# Sheet1.net
KiCad netlist of a schematic drawn in Altium Designer
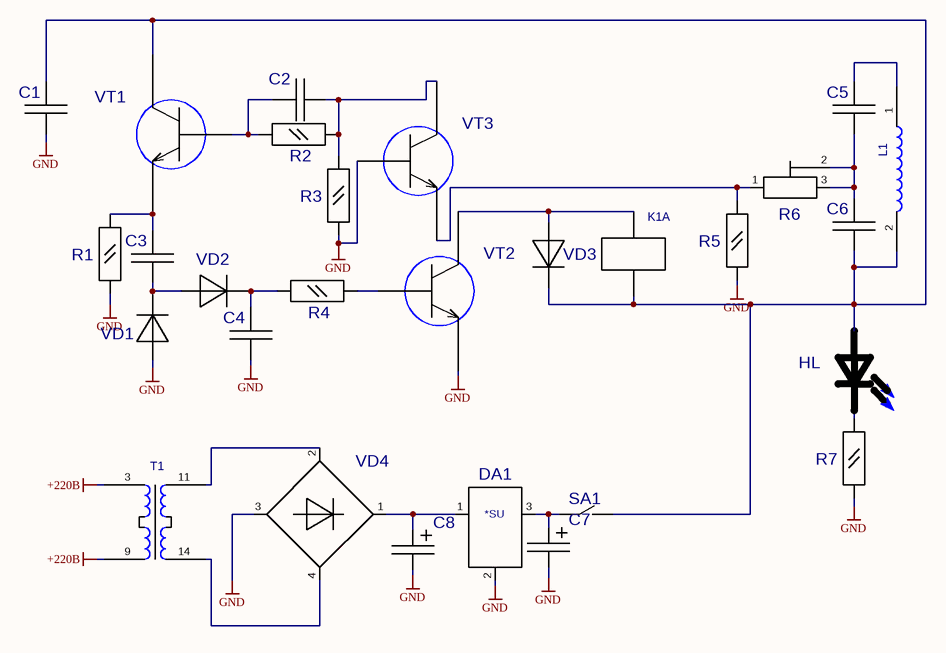
[diagram p0: Sheet1.SCHDOC]

(export (version "E")
  (design (tool "Eeschema 10.0.6"))
  (components
    (comp (ref "C1")
      (value "B32921-C3103-0,01UF")
      (footprint "B32921(13X4)")
      (libsource (lib "*") (part "B32921-C3103-0,01UF"))
    )
    (comp (ref "C2")
      (value "B32921-C3103-0,01UF")
      (footprint "B32921(13X4)")
      (libsource (lib "*") (part "B32921-C3103-0,01UF"))
    )
    (comp (ref "C3")
      (value "B32921-C3103-0,01UF")
      (footprint "B32921(13X4)")
      (libsource (lib "*") (part "B32921-C3103-0,01UF"))
    )
    (comp (ref "C4")
      (value "B32921-C3103-0,01UF")
      (footprint "B32921(13X4)")
      (libsource (lib "*") (part "B32921-C3103-0,01UF"))
    )
    (comp (ref "C5")
      (value "B32921-C3103-0,01UF")
      (footprint "B32921(13X4)")
      (libsource (lib "*") (part "B32921-C3103-0,01UF"))
    )
    (comp (ref "C6")
      (value "B32921-C3103-0,01UF")
      (footprint "B32921(13X4)")
      (libsource (lib "*") (part "B32921-C3103-0,01UF"))
    )
    (comp (ref "C7") (value "COND-PL-EL") (footprint "CC-PL-EL1") (libsource (lib "*") (part "COND-PL-EL")))
    (comp (ref "C8") (value "COND-PL-EL") (footprint "CC-PL-EL1") (libsource (lib "*") (part "COND-PL-EL")))
    (comp (ref "DA1") (value "KR142EN") (footprint "KR142EN") (libsource (lib "*") (part "KR142EN")))
    (comp (ref "HL") (value "КИПД21-К") (footprint "LED-5MM") (libsource (lib "*") (part "КИПД21-К")))
    (comp (ref "K1") (value "РЭС6") (footprint "РЭС6") (libsource (lib "*") (part "РЭС6")))
    (comp (ref "L1") (value "L") (footprint "L") (libsource (lib "*") (part "L")))
    (comp (ref "R1")
      (value "C2-33H-0.125W_OLD_UGO")
      (footprint "C2-33H-0.125W")
      (fields (field (name "AUTOR") "pcbdesigner.ru"))
      (libsource (lib "*") (part "C2-33H-0.125W_OLD_UGO"))
    )
    (comp (ref "R2")
      (value "C2-33H-0.125W_OLD_UGO")
      (footprint "C2-33H-0.125W")
      (fields (field (name "AUTOR") "pcbdesigner.ru"))
      (libsource (lib "*") (part "C2-33H-0.125W_OLD_UGO"))
    )
    (comp (ref "R3")
      (value "C2-33H-0.125W_OLD_UGO")
      (footprint "C2-33H-0.125W")
      (fields (field (name "AUTOR") "pcbdesigner.ru"))
      (libsource (lib "*") (part "C2-33H-0.125W_OLD_UGO"))
    )
    (comp (ref "R4")
      (value "C2-33H-0.125W_OLD_UGO")
      (footprint "C2-33H-0.125W")
      (fields (field (name "AUTOR") "pcbdesigner.ru"))
      (libsource (lib "*") (part "C2-33H-0.125W_OLD_UGO"))
    )
    (comp (ref "R5")
      (value "C2-33H-0.125W_OLD_UGO")
      (footprint "C2-33H-0.125W")
      (fields (field (name "AUTOR") "pcbdesigner.ru"))
      (libsource (lib "*") (part "C2-33H-0.125W_OLD_UGO"))
    )
    (comp (ref "R6") (value "SP3-19A1") (footprint "SP3-19A1") (libsource (lib "*") (part "SP3-19A1")))
    (comp (ref "R7")
      (value "C2-33H-0.125W_OLD_UGO")
      (footprint "C2-33H-0.125W")
      (fields (field (name "AUTOR") "pcbdesigner.ru"))
      (libsource (lib "*") (part "C2-33H-0.125W_OLD_UGO"))
    )
    (comp (ref "SA1")
      (value "8AS9M2RE")
      (footprint "8AS9M2RE")
      (fields (field (name "AUTHOR") "pcbdesigner.ru"))
      (libsource (lib "*") (part "8AS9M2RE"))
    )
    (comp (ref "T1") (value "ТПП277") (footprint "ТПП") (libsource (lib "*") (part "ТПП277")))
    (comp (ref "VD1") (value "DO27") (footprint "DO27") (libsource (lib "*") (part "DO27")))
    (comp (ref "VD2") (value "DO27") (footprint "DO27") (libsource (lib "*") (part "DO27")))
    (comp (ref "VD3") (value "DO27") (footprint "DO27") (libsource (lib "*") (part "DO27")))
    (comp (ref "VD4") (value "KBU6A") (footprint "KBU6A") (libsource (lib "*") (part "KBU6A")))
    (comp (ref "VT1") (value "2N4401") (footprint "TO-92-1") (libsource (lib "*") (part "2N4401")))
    (comp (ref "VT2") (value "2N4401") (footprint "TO-92-1") (libsource (lib "*") (part "2N4401")))
    (comp (ref "VT3") (value "2N4401") (footprint "TO-92-1") (libsource (lib "*") (part "2N4401")))
  )
  (nets
    (net (code "1") (name "+220B") (class "Default")
      (node (ref "T1") (pin "3") (pintype "passive"))
      (node (ref "T1") (pin "9") (pintype "passive"))
    )
    (net (code "2") (name "GND") (class "Default")
      (node (ref "C1") (pin "2") (pinfunction "2_2") (pintype "passive"))
      (node (ref "C4") (pin "2") (pinfunction "2_2") (pintype "passive"))
      (node (ref "C7") (pin "2") (pinfunction "i/o1_2") (pintype "passive"))
      (node (ref "C8") (pin "2") (pinfunction "i/o1_2") (pintype "passive"))
      (node (ref "DA1") (pin "2") (pinfunction "GND0_2") (pintype "passive"))
      (node (ref "R1") (pin "2") (pinfunction "2_2") (pintype "passive"))
      (node (ref "R3") (pin "2") (pinfunction "2_2") (pintype "passive"))
      (node (ref "R5") (pin "2") (pinfunction "2_2") (pintype "passive"))
      (node (ref "R7") (pin "2") (pinfunction "2_2") (pintype "passive"))
      (node (ref "VD1") (pin "2") (pinfunction "I/O2_2") (pintype "passive"))
      (node (ref "VD4") (pin "3") (pinfunction "3_3") (pintype "passive"))
      (node (ref "VT2") (pin "1") (pinfunction "E_1") (pintype "passive"))
      (node (ref "VT3") (pin "2") (pinfunction "B_2") (pintype "passive"))
    )
    (net (code "3") (name "Net-(C5-Pad1)") (class "Default")
      (node (ref "C5") (pin "1") (pinfunction "1_1") (pintype "passive"))
      (node (ref "L1") (pin "1") (pintype "passive"))
    )
    (net (code "4") (name "Net-(C7-i{slash}o)") (class "Default")
      (node (ref "C7") (pin "1") (pinfunction "i/o_1") (pintype "passive"))
      (node (ref "DA1") (pin "3") (pinfunction "OUT0_3") (pintype "passive"))
      (node (ref "SA1") (pin "2") (pinfunction "2_2") (pintype "passive"))
    )
    (net (code "5") (name "Net-(C8-i{slash}o)") (class "Default")
      (node (ref "C8") (pin "1") (pinfunction "i/o_1") (pintype "passive"))
      (node (ref "DA1") (pin "1") (pinfunction "IN0_1") (pintype "passive"))
      (node (ref "VD4") (pin "1") (pinfunction "1_1") (pintype "passive"))
    )
    (net (code "6") (name "Net-(HL-A)") (class "Default")
      (node (ref "C1") (pin "1") (pinfunction "1_1") (pintype "passive"))
      (node (ref "C6") (pin "2") (pinfunction "2_2") (pintype "passive"))
      (node (ref "HL") (pin "1") (pinfunction "A_1") (pintype "passive"))
      (node (ref "K1") (pin "8") (pinfunction "3_8") (pintype "passive"))
      (node (ref "L1") (pin "2") (pintype "passive"))
      (node (ref "SA1") (pin "1") (pinfunction "1_1") (pintype "passive"))
      (node (ref "VD3") (pin "1") (pinfunction "I/O1_1") (pintype "passive"))
      (node (ref "VT1") (pin "3") (pinfunction "K_3") (pintype "passive"))
    )
    (net (code "7") (name "Net-(HL-K)") (class "Default")
      (node (ref "HL") (pin "2") (pinfunction "K_2") (pintype "passive"))
      (node (ref "R7") (pin "1") (pinfunction "1_1") (pintype "passive"))
    )
    (net (code "8") (name "Net-(K1-1)") (class "Default")
      (node (ref "K1") (pin "7") (pinfunction "1_7") (pintype "passive"))
      (node (ref "VD3") (pin "2") (pinfunction "I/O2_2") (pintype "passive"))
      (node (ref "VT2") (pin "3") (pinfunction "K_3") (pintype "passive"))
    )
    (net (code "9") (name "Net-(R6-I{slash}O1)") (class "Default")
      (node (ref "R5") (pin "1") (pinfunction "1_1") (pintype "passive"))
      (node (ref "R6") (pin "1") (pinfunction "I/O1_1") (pintype "passive"))
      (node (ref "VT3") (pin "1") (pinfunction "E_1") (pintype "passive"))
    )
    (net (code "10") (name "Net-(R6-I{slash}O2)") (class "Default")
      (node (ref "C5") (pin "2") (pinfunction "2_2") (pintype "passive"))
      (node (ref "C6") (pin "1") (pinfunction "1_1") (pintype "passive"))
      (node (ref "R6") (pin "2") (pinfunction "I/O2_2") (pintype "passive"))
      (node (ref "R6") (pin "3") (pinfunction "I/O3_3") (pintype "passive"))
    )
    (net (code "11") (name "Net-(T1-Pad11)") (class "Default")
      (node (ref "T1") (pin "11") (pintype "passive"))
      (node (ref "VD4") (pin "2") (pinfunction "2_2") (pintype "passive"))
    )
    (net (code "12") (name "Net-(T1-Pad14)") (class "Default")
      (node (ref "T1") (pin "14") (pintype "passive"))
      (node (ref "VD4") (pin "4") (pinfunction "4_4") (pintype "passive"))
    )
    (net (code "13") (name "Net-(VD1-I{slash}O1)") (class "Default")
      (node (ref "C3") (pin "2") (pinfunction "2_2") (pintype "passive"))
      (node (ref "VD1") (pin "1") (pinfunction "I/O1_1") (pintype "passive"))
      (node (ref "VD2") (pin "2") (pinfunction "I/O2_2") (pintype "passive"))
    )
    (net (code "14") (name "Net-(VD2-I{slash}O1)") (class "Default")
      (node (ref "C4") (pin "1") (pinfunction "1_1") (pintype "passive"))
      (node (ref "R4") (pin "1") (pinfunction "1_1") (pintype "passive"))
      (node (ref "VD2") (pin "1") (pinfunction "I/O1_1") (pintype "passive"))
    )
    (net (code "15") (name "Net-(VT1-B)") (class "Default")
      (node (ref "C2") (pin "1") (pinfunction "1_1") (pintype "passive"))
      (node (ref "R2") (pin "1") (pinfunction "1_1") (pintype "passive"))
      (node (ref "VT1") (pin "2") (pinfunction "B_2") (pintype "passive"))
    )
    (net (code "16") (name "Net-(VT1-E)") (class "Default")
      (node (ref "C3") (pin "1") (pinfunction "1_1") (pintype "passive"))
      (node (ref "R1") (pin "1") (pinfunction "1_1") (pintype "passive"))
      (node (ref "VT1") (pin "1") (pinfunction "E_1") (pintype "passive"))
    )
    (net (code "17") (name "Net-(VT2-B)") (class "Default")
      (node (ref "R4") (pin "2") (pinfunction "2_2") (pintype "passive"))
      (node (ref "VT2") (pin "2") (pinfunction "B_2") (pintype "passive"))
    )
    (net (code "18") (name "Net-(VT3-K)") (class "Default")
      (node (ref "C2") (pin "2") (pinfunction "2_2") (pintype "passive"))
      (node (ref "R2") (pin "2") (pinfunction "2_2") (pintype "passive"))
      (node (ref "R3") (pin "1") (pinfunction "1_1") (pintype "passive"))
      (node (ref "VT3") (pin "3") (pinfunction "K_3") (pintype "passive"))
    )
  )
)
